# IR_Prox_Sensor.net
KiCad netlist of a schematic drawn in Altium Designer
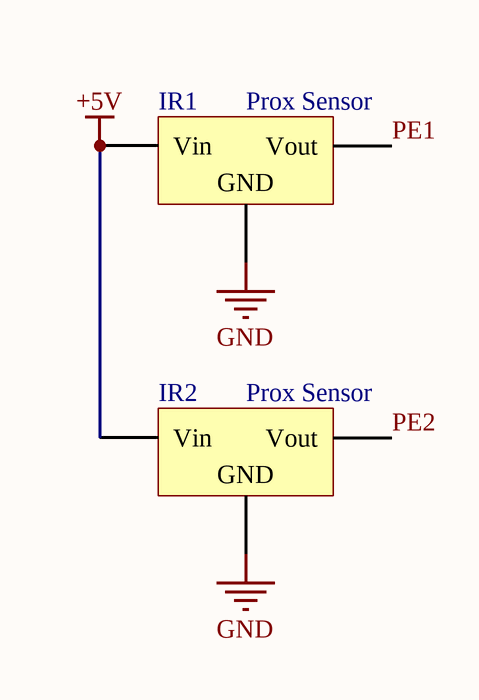
[diagram p0: IR Prox Sensor.SchDoc]

(export (version "E")
  (design (tool "Eeschema 10.0.6"))
  (components
    (comp (ref "IR1")
      (value "Prox Sensor")
      (footprint "D2PAK_L")
      (description "Voltage Regulator")
      (fields (field (name "PUBLISHER") "Altium Limited"))
      (libsource (lib "Miscellaneous Devices") (part "Volt Reg"))
    )
    (comp (ref "IR2")
      (value "Prox Sensor")
      (footprint "D2PAK_L")
      (description "Voltage Regulator")
      (fields (field (name "PUBLISHER") "Altium Limited"))
      (libsource (lib "Miscellaneous Devices") (part "Volt Reg"))
    )
  )
  (nets
    (net (code "1") (name "+5V") (class "Default")
      (node (ref "IR1") (pin "1") (pinfunction "Vin_1") (pintype "passive"))
      (node (ref "IR2") (pin "1") (pinfunction "Vin_1") (pintype "passive"))
    )
    (net (code "2") (name "/PE1") (class "Default")
      (node (ref "IR1") (pin "3") (pinfunction "Vout_3") (pintype "passive"))
    )
    (net (code "3") (name "/PE2") (class "Default")
      (node (ref "IR2") (pin "3") (pinfunction "Vout_3") (pintype "passive"))
    )
    (net (code "4") (name "GND") (class "Default")
      (node (ref "IR1") (pin "2") (pinfunction "GND_2") (pintype "passive"))
      (node (ref "IR2") (pin "2") (pinfunction "GND_2") (pintype "passive"))
    )
  )
)
